# Library_v47.net
KiCad netlist of a schematic drawn in EAGLE
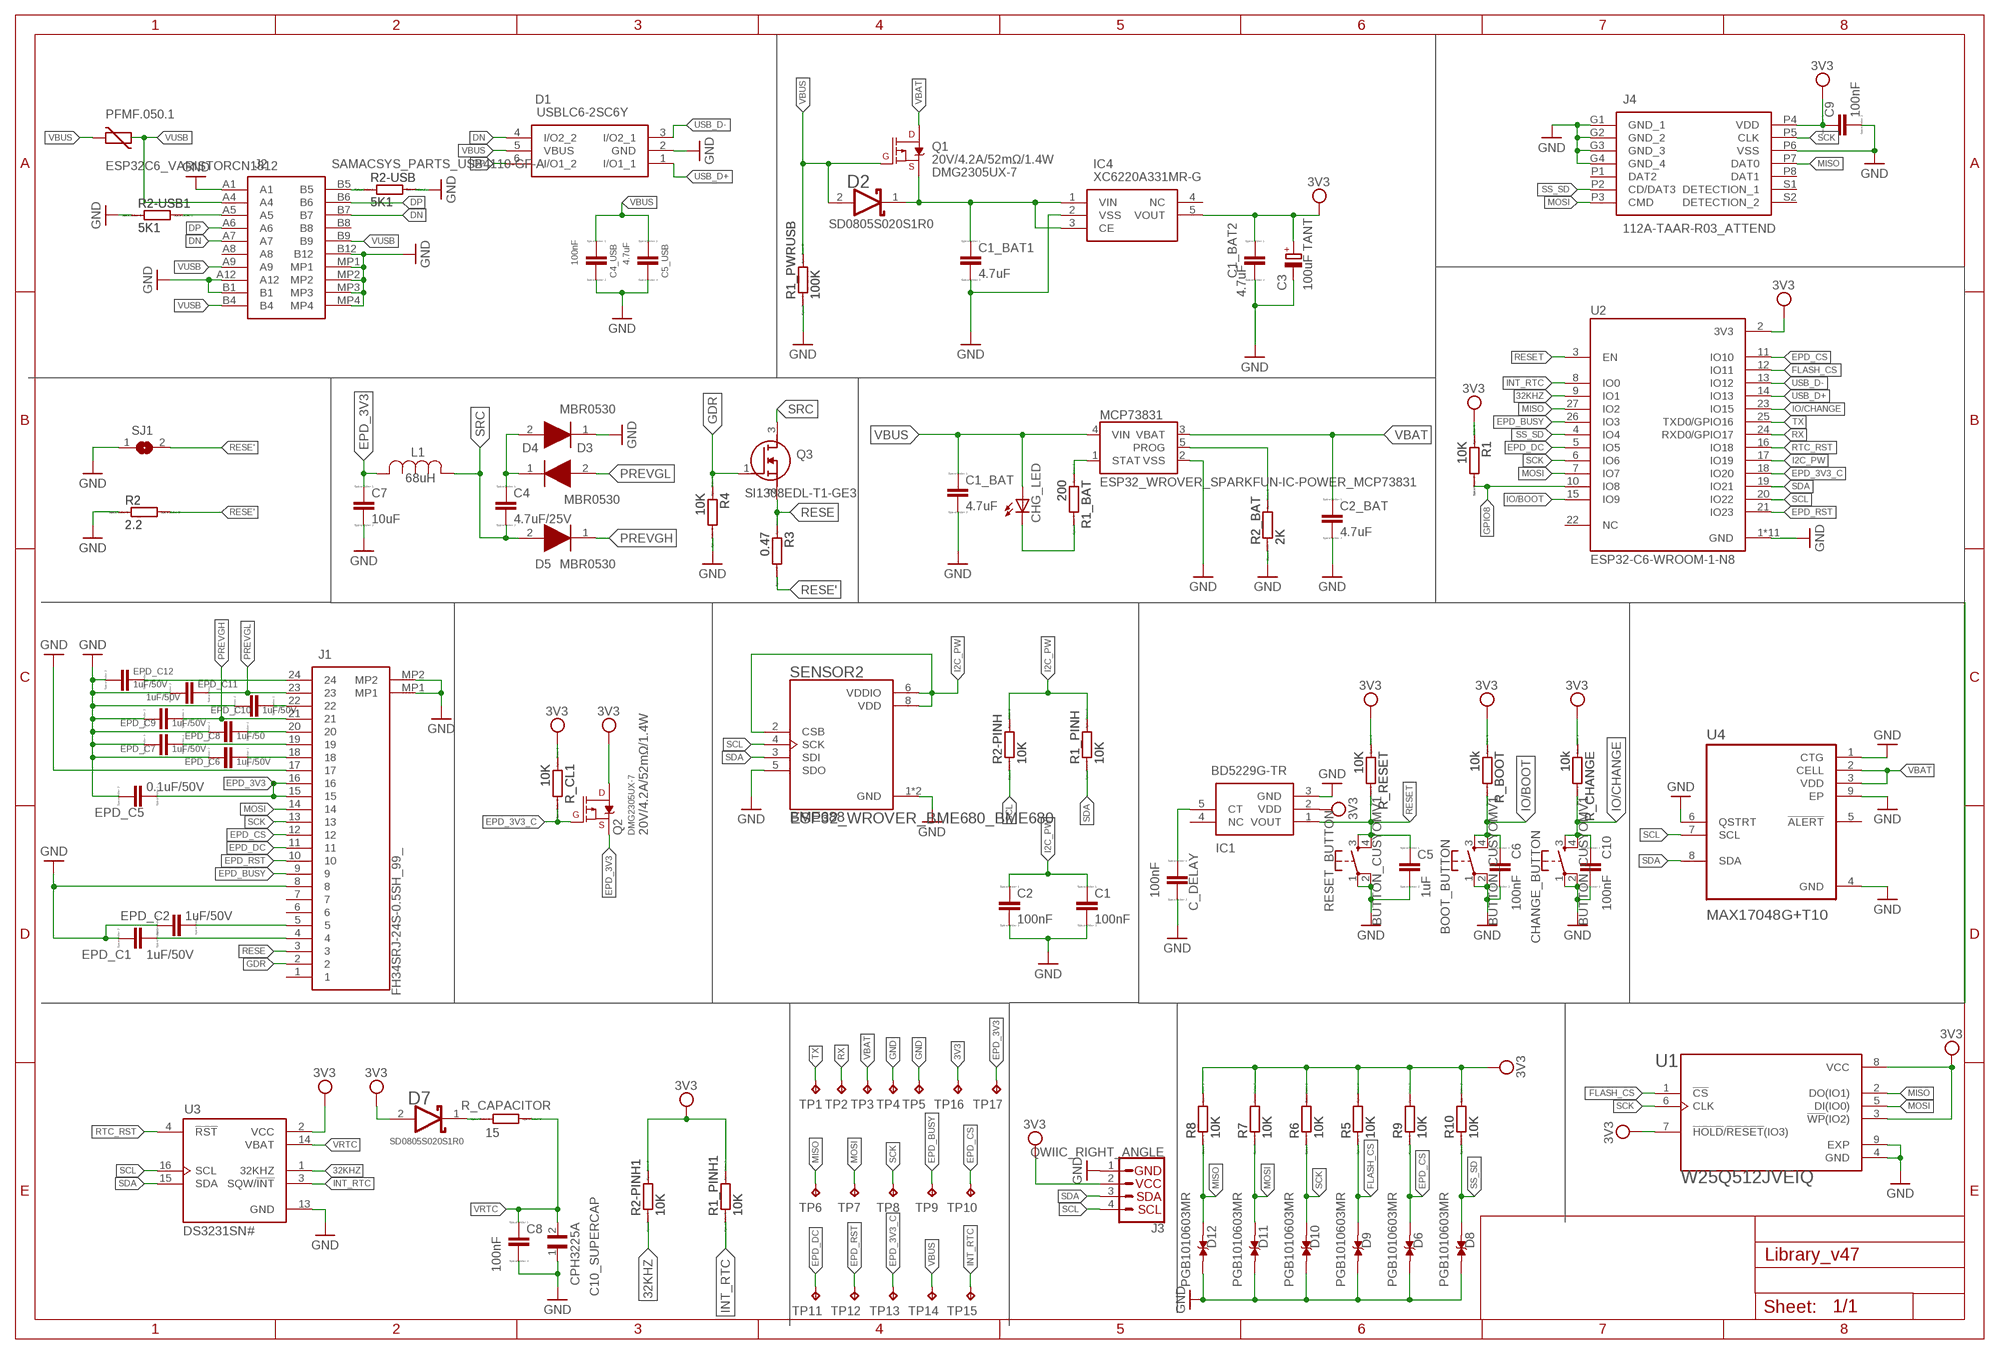
[diagram p0: schematic, sheet 1]

(export (version "E")
  (design (tool "Eeschema 10.0.6"))
  (components
    (comp (ref "BOOT_BUTTON")
      (value "BUTTON_CUSYOMV1")
      (footprint "eagle-import:MYBUTTON")
      (libsource (lib "eagle-import") (part "BUTTON_CUSYOMV1"))
    )
    (comp (ref "C1")
      (value "100nF")
      (footprint "eagle-import:ESP32_WROVER_EAGLE-LTSPICE_C0402")
      (libsource (lib "eagle-import") (part "ESP32_WROVER_EAGLE-LTSPICE_CC0402"))
    )
    (comp (ref "C1_BAT")
      (value "4.7uF")
      (footprint "eagle-import:ESP32_WROVER_EAGLE-LTSPICE_C0402")
      (libsource (lib "eagle-import") (part "ESP32_WROVER_EAGLE-LTSPICE_CC0402"))
    )
    (comp (ref "C1_BAT1")
      (value "4.7uF")
      (footprint "eagle-import:ESP32_WROVER_EAGLE-LTSPICE_C0402")
      (libsource (lib "eagle-import") (part "ESP32_WROVER_EAGLE-LTSPICE_CC0402"))
    )
    (comp (ref "C1_BAT2")
      (value "4.7uF")
      (footprint "eagle-import:ESP32_WROVER_EAGLE-LTSPICE_C0402")
      (libsource (lib "eagle-import") (part "ESP32_WROVER_EAGLE-LTSPICE_CC0402"))
    )
    (comp (ref "C2")
      (value "100nF")
      (footprint "eagle-import:ESP32_WROVER_EAGLE-LTSPICE_C0402")
      (libsource (lib "eagle-import") (part "ESP32_WROVER_EAGLE-LTSPICE_CC0402"))
    )
    (comp (ref "C2_BAT")
      (value "4.7uF")
      (footprint "eagle-import:ESP32_WROVER_EAGLE-LTSPICE_C0402")
      (libsource (lib "eagle-import") (part "ESP32_WROVER_EAGLE-LTSPICE_CC0402"))
    )
    (comp (ref "C3")
      (value "100uF TANT")
      (footprint "eagle-import:RCL_CT3528")
      (libsource (lib "eagle-import") (part "RCL_CPOL-EUCT3528"))
    )
    (comp (ref "C4")
      (value "4.7uF/25V")
      (footprint "eagle-import:ESP32_WROVER_EAGLE-LTSPICE_C0402")
      (libsource (lib "eagle-import") (part "ESP32_WROVER_EAGLE-LTSPICE_CC0402"))
    )
    (comp (ref "C4_USB")
      (value "100nF")
      (footprint "eagle-import:ESP32_WROVER_EAGLE-LTSPICE_C0402")
      (libsource (lib "eagle-import") (part "ESP32_WROVER_EAGLE-LTSPICE_CC0402"))
    )
    (comp (ref "C5")
      (value "1uF")
      (footprint "eagle-import:ESP32_WROVER_EAGLE-LTSPICE_C0402")
      (libsource (lib "eagle-import") (part "ESP32_WROVER_EAGLE-LTSPICE_CC0402"))
    )
    (comp (ref "C5_USB")
      (value "4.7uF")
      (footprint "eagle-import:ESP32_WROVER_EAGLE-LTSPICE_C0402")
      (libsource (lib "eagle-import") (part "ESP32_WROVER_EAGLE-LTSPICE_CC0402"))
    )
    (comp (ref "C6")
      (value "100nF")
      (footprint "eagle-import:ESP32_WROVER_EAGLE-LTSPICE_C0402")
      (libsource (lib "eagle-import") (part "ESP32_WROVER_EAGLE-LTSPICE_CC0402"))
    )
    (comp (ref "C7")
      (value "10uF")
      (footprint "eagle-import:ESP32_WROVER_EAGLE-LTSPICE_C0402")
      (libsource (lib "eagle-import") (part "ESP32_WROVER_EAGLE-LTSPICE_CC0402"))
    )
    (comp (ref "C8")
      (value "100nF")
      (footprint "eagle-import:ESP32_WROVER_EAGLE-LTSPICE_C0402")
      (libsource (lib "eagle-import") (part "ESP32_WROVER_EAGLE-LTSPICE_CC0402"))
    )
    (comp (ref "C9")
      (value "100nF")
      (footprint "eagle-import:ESP32_WROVER_EAGLE-LTSPICE_C0402")
      (libsource (lib "eagle-import") (part "ESP32_WROVER_EAGLE-LTSPICE_CC0402"))
    )
    (comp (ref "C10")
      (value "100nF")
      (footprint "eagle-import:ESP32_WROVER_EAGLE-LTSPICE_C0402")
      (libsource (lib "eagle-import") (part "ESP32_WROVER_EAGLE-LTSPICE_CC0402"))
    )
    (comp (ref "C10_SUPERCAP")
      (value "CPH3225A")
      (footprint "eagle-import:CAPCP3225X100N")
      (fields (field (name "MF") "Seiko Instruments"))
      (libsource (lib "eagle-import") (part "CPH3225A"))
    )
    (comp (ref "CHANGE_BUTTON")
      (value "BUTTON_CUSYOMV1")
      (footprint "eagle-import:MYBUTTON")
      (libsource (lib "eagle-import") (part "BUTTON_CUSYOMV1"))
    )
    (comp (ref "CHG_LED")
      (value "ADAFRUIT_LEDCHIP-LED0603")
      (footprint "eagle-import:ADAFRUIT_CHIP-LED0603")
      (libsource (lib "eagle-import") (part "ADAFRUIT_LEDCHIP-LED0603"))
    )
    (comp (ref "C_DELAY")
      (value "100nF")
      (footprint "eagle-import:ESP32_WROVER_EAGLE-LTSPICE_C0402")
      (libsource (lib "eagle-import") (part "ESP32_WROVER_EAGLE-LTSPICE_CC0402"))
    )
    (comp (ref "D1")
      (value "USBLC6-2SC6Y")
      (footprint "eagle-import:SOT95P280X145-6N")
      (fields (field (name "MF") "STMicroelectronics"))
      (libsource (lib "eagle-import") (part "USBLC6-2SC6Y"))
    )
    (comp (ref "D2")
      (value "ESP32_WROVER_AVX---SD0805S020S1R0_AVX_SD0805S020S1R0_0_0AVX_SD0805S020S1R0_0_0")
      (footprint "eagle-import:ESP32_WROVER_AVX---SD0805S020S1R0_AVX_SD0805S020S1R0_0")
      (fields
        (field (name "DIGIKEY_PART_NUMBER") "478-7800-1-ND")
        (field (name "MF") "AVX")
        (field (name "MOUSER_PART_NUMBER") "581-SD0805S020S1R0")
      )
      (libsource (lib "eagle-import") (part "ESP32_WROVER_AVX---SD0805S020S1R0_AVX_SD0805S020S1R0_0_0AVX_SD0805S020S1R0_0_0"))
    )
    (comp (ref "D3")
      (value "MBR0530")
      (footprint "eagle-import:SOD3716X135N")
      (fields (field (name "MF") "ON Semiconductor"))
      (libsource (lib "eagle-import") (part "MBR0530"))
    )
    (comp (ref "D4")
      (value "MBR0530")
      (footprint "eagle-import:SOD3716X135N")
      (fields (field (name "MF") "ON Semiconductor"))
      (libsource (lib "eagle-import") (part "MBR0530"))
    )
    (comp (ref "D5")
      (value "MBR0530")
      (footprint "eagle-import:SOD3716X135N")
      (fields (field (name "MF") "ON Semiconductor"))
      (libsource (lib "eagle-import") (part "MBR0530"))
    )
    (comp (ref "D6")
      (value "PGB1010603MR")
      (footprint "eagle-import:DIOC1608X36N")
      (fields (field (name "MF") "Littelfuse Inc."))
      (libsource (lib "eagle-import") (part "PGB1010603MR"))
    )
    (comp (ref "D7")
      (value "ESP32_WROVER_AVX---SD0805S020S1R0_AVX_SD0805S020S1R0_0_0AVX_SD0805S020S1R0_0_0")
      (footprint "eagle-import:ESP32_WROVER_AVX---SD0805S020S1R0_AVX_SD0805S020S1R0_0")
      (fields
        (field (name "DIGIKEY_PART_NUMBER") "478-7800-1-ND")
        (field (name "MF") "AVX")
        (field (name "MOUSER_PART_NUMBER") "581-SD0805S020S1R0")
      )
      (libsource (lib "eagle-import") (part "ESP32_WROVER_AVX---SD0805S020S1R0_AVX_SD0805S020S1R0_0_0AVX_SD0805S020S1R0_0_0"))
    )
    (comp (ref "D8")
      (value "PGB1010603MR")
      (footprint "eagle-import:DIOC1608X36N")
      (fields (field (name "MF") "Littelfuse Inc."))
      (libsource (lib "eagle-import") (part "PGB1010603MR"))
    )
    (comp (ref "D9")
      (value "PGB1010603MR")
      (footprint "eagle-import:DIOC1608X36N")
      (fields (field (name "MF") "Littelfuse Inc."))
      (libsource (lib "eagle-import") (part "PGB1010603MR"))
    )
    (comp (ref "D10")
      (value "PGB1010603MR")
      (footprint "eagle-import:DIOC1608X36N")
      (fields (field (name "MF") "Littelfuse Inc."))
      (libsource (lib "eagle-import") (part "PGB1010603MR"))
    )
    (comp (ref "D11")
      (value "PGB1010603MR")
      (footprint "eagle-import:DIOC1608X36N")
      (fields (field (name "MF") "Littelfuse Inc."))
      (libsource (lib "eagle-import") (part "PGB1010603MR"))
    )
    (comp (ref "D12")
      (value "PGB1010603MR")
      (footprint "eagle-import:DIOC1608X36N")
      (fields (field (name "MF") "Littelfuse Inc."))
      (libsource (lib "eagle-import") (part "PGB1010603MR"))
    )
    (comp (ref "EPD_C1")
      (value "1uF/50V")
      (footprint "eagle-import:ESP32_WROVER_EAGLE-LTSPICE_C0402")
      (libsource (lib "eagle-import") (part "ESP32_WROVER_EAGLE-LTSPICE_CC0402"))
    )
    (comp (ref "EPD_C2")
      (value "1uF/50V")
      (footprint "eagle-import:ESP32_WROVER_EAGLE-LTSPICE_C0402")
      (libsource (lib "eagle-import") (part "ESP32_WROVER_EAGLE-LTSPICE_CC0402"))
    )
    (comp (ref "EPD_C5")
      (value "0.1uF/50V")
      (footprint "eagle-import:ESP32_WROVER_EAGLE-LTSPICE_C0402")
      (libsource (lib "eagle-import") (part "ESP32_WROVER_EAGLE-LTSPICE_CC0402"))
    )
    (comp (ref "EPD_C6")
      (value "1uF/50V")
      (footprint "eagle-import:ESP32_WROVER_EAGLE-LTSPICE_C0402")
      (libsource (lib "eagle-import") (part "ESP32_WROVER_EAGLE-LTSPICE_CC0402"))
    )
    (comp (ref "EPD_C7")
      (value "1uF/50V")
      (footprint "eagle-import:ESP32_WROVER_EAGLE-LTSPICE_C0402")
      (libsource (lib "eagle-import") (part "ESP32_WROVER_EAGLE-LTSPICE_CC0402"))
    )
    (comp (ref "EPD_C8")
      (value "1uF/50")
      (footprint "eagle-import:ESP32_WROVER_EAGLE-LTSPICE_C0402")
      (libsource (lib "eagle-import") (part "ESP32_WROVER_EAGLE-LTSPICE_CC0402"))
    )
    (comp (ref "EPD_C9")
      (value "1uF/50V")
      (footprint "eagle-import:ESP32_WROVER_EAGLE-LTSPICE_C0402")
      (libsource (lib "eagle-import") (part "ESP32_WROVER_EAGLE-LTSPICE_CC0402"))
    )
    (comp (ref "EPD_C10")
      (value "1uF/50V")
      (footprint "eagle-import:ESP32_WROVER_EAGLE-LTSPICE_C0402")
      (libsource (lib "eagle-import") (part "ESP32_WROVER_EAGLE-LTSPICE_CC0402"))
    )
    (comp (ref "EPD_C11")
      (value "1uF/50V")
      (footprint "eagle-import:ESP32_WROVER_EAGLE-LTSPICE_C0402")
      (libsource (lib "eagle-import") (part "ESP32_WROVER_EAGLE-LTSPICE_CC0402"))
    )
    (comp (ref "EPD_C12")
      (value "1uF/50V")
      (footprint "eagle-import:ESP32_WROVER_EAGLE-LTSPICE_C0402")
      (libsource (lib "eagle-import") (part "ESP32_WROVER_EAGLE-LTSPICE_CC0402"))
    )
    (comp (ref "IC1")
      (value "BD5229G-TR")
      (footprint "eagle-import:SOT95P280X125-5N")
      (fields (field (name "MOUSER_PART_NUMBER") "755-BD5229G-TR"))
      (libsource (lib "eagle-import") (part "BD5229G-TR"))
    )
    (comp (ref "IC4")
      (value "XC6220A331MR-G")
      (footprint "eagle-import:SOT95P280X120-5N")
      (fields (field (name "MOUSER_PART_NUMBER") "865-XC6220A331MR-G"))
      (libsource (lib "eagle-import") (part "XC6220A331MR-G"))
    )
    (comp (ref "J1")
      (value "FH34SRJ-24S-0.5SH_99_")
      (footprint "eagle-import:FH34SRJ24S05SH99")
      (fields
        (field (name "MANUFACTURER_PART_NUMBER") "FH34SRJ-24S-0.5SH(99)")
        (field (name "MOUSER_PART_NUMBER") "798-FH34SRJ24S05SH99")
      )
      (libsource (lib "eagle-import") (part "FH34SRJ-24S-0.5SH_99_"))
    )
    (comp (ref "J2")
      (value "SAMACSYS_PARTS_USB4110-GF-A")
      (footprint "eagle-import:SAMACSYS_PARTS_USB4110GFA")
      (fields
        (field (name "MANUFACTURER_PART_NUMBER") "USB4110-GF-A")
        (field (name "MOUSER_PART_NUMBER") "640-USB4110-GF-A")
      )
      (libsource (lib "eagle-import") (part "SAMACSYS_PARTS_USB4110-GF-A"))
    )
    (comp (ref "J3")
      (value "QWIIC_RIGHT_ANGLE")
      (footprint "eagle-import:JST04_1MM_RA")
      (libsource (lib "eagle-import") (part "QWIIC_CONNECTORJS-1MM"))
    )
    (comp (ref "J4")
      (value "112A-TAAR-R03_ATTEND")
      (footprint "eagle-import:112ATAARR03ATTEND")
      (fields (field (name "MANUFACTURER_PART_NUMBER") "112A-TAAR-R03 ATTEND"))
      (libsource (lib "eagle-import") (part "112A-TAAR-R03_ATTEND"))
    )
    (comp (ref "L1")
      (value "68uH")
      (footprint "eagle-import:IND_4828-WE-TPC_WRE")
      (fields
        (field (name "MANUFACTURER_PART_NUMBER") "744043680")
        (field (name "COPYRIGHT") "Copyright (C) 2024 Ultra Librarian. All rights reserved.")
      )
      (libsource (lib "eagle-import") (part "744043680IND_4828-WE-TPC_WRE"))
    )
    (comp (ref "MCP73831")
      (value "ESP32_WROVER_SPARKFUN-IC-POWER_MCP73831")
      (footprint "eagle-import:ESP32_WROVER_SPARKFUN-IC-POWER_SOT23-5")
      (libsource (lib "eagle-import") (part "ESP32_WROVER_SPARKFUN-IC-POWER_MCP73831"))
    )
    (comp (ref "PFMF.050.1")
      (value "ESP32C6_VARISTORCN1812")
      (footprint "eagle-import:ESP32C6_VARISTOR_CT_CN1812")
      (libsource (lib "eagle-import") (part "ESP32C6_VARISTORCN1812"))
    )
    (comp (ref "Q1")
      (value "20V/4.2A/52mΩ/1.4W")
      (footprint "eagle-import:ESP32_WROVER_SPARKFUN-DISCRETESEMI_SOT23-3")
      (libsource (lib "eagle-import") (part "ESP32_WROVER_SPARKFUN-DISCRETESEMI_MOSFET_PCH-DMG2305UX-7"))
    )
    (comp (ref "Q2")
      (value "20V/4.2A/52mΩ/1.4W")
      (footprint "eagle-import:ESP32_WROVER_SPARKFUN-DISCRETESEMI_SOT23-3")
      (libsource (lib "eagle-import") (part "ESP32_WROVER_SPARKFUN-DISCRETESEMI_MOSFET_PCH-DMG2305UX-7"))
    )
    (comp (ref "Q3")
      (value "SI1308EDL-T1-GE3")
      (footprint "eagle-import:SOT65P210X110-3N")
      (fields (field (name "MF") "Vishay Siliconix"))
      (libsource (lib "eagle-import") (part "SI1308EDL-T1-GE3"))
    )
    (comp (ref "R1")
      (value "10K")
      (footprint "eagle-import:ESP32_WROVER_EAGLE-LTSPICE_R0402")
      (libsource (lib "eagle-import") (part "ESP32_WROVER_EAGLE-LTSPICE_RR0402"))
    )
    (comp (ref "R1_BAT")
      (value "200")
      (footprint "eagle-import:ESP32_WROVER_EAGLE-LTSPICE_R0402")
      (libsource (lib "eagle-import") (part "ESP32_WROVER_EAGLE-LTSPICE_RR0402"))
    )
    (comp (ref "R1_PINH")
      (value "10K")
      (footprint "eagle-import:ESP32_WROVER_EAGLE-LTSPICE_R0402")
      (libsource (lib "eagle-import") (part "ESP32_WROVER_EAGLE-LTSPICE_RR0402"))
    )
    (comp (ref "R1_PINH1")
      (value "10K")
      (footprint "eagle-import:ESP32_WROVER_EAGLE-LTSPICE_R0402")
      (libsource (lib "eagle-import") (part "ESP32_WROVER_EAGLE-LTSPICE_RR0402"))
    )
    (comp (ref "R1_PWRUSB")
      (value "100K")
      (footprint "eagle-import:ESP32_WROVER_EAGLE-LTSPICE_R0402")
      (libsource (lib "eagle-import") (part "ESP32_WROVER_EAGLE-LTSPICE_RR0402"))
    )
    (comp (ref "R2")
      (value "2.2")
      (footprint "eagle-import:ESP32_WROVER_EAGLE-LTSPICE_R0402")
      (libsource (lib "eagle-import") (part "ESP32_WROVER_EAGLE-LTSPICE_RR0402"))
    )
    (comp (ref "R2-PINH")
      (value "10K")
      (footprint "eagle-import:ESP32_WROVER_EAGLE-LTSPICE_R0402")
      (libsource (lib "eagle-import") (part "ESP32_WROVER_EAGLE-LTSPICE_RR0402"))
    )
    (comp (ref "R2-PINH1")
      (value "10K")
      (footprint "eagle-import:ESP32_WROVER_EAGLE-LTSPICE_R0402")
      (libsource (lib "eagle-import") (part "ESP32_WROVER_EAGLE-LTSPICE_RR0402"))
    )
    (comp (ref "R2-USB")
      (value "5K1")
      (footprint "eagle-import:ESP32_WROVER_EAGLE-LTSPICE_R0402")
      (libsource (lib "eagle-import") (part "ESP32_WROVER_EAGLE-LTSPICE_RR0402"))
    )
    (comp (ref "R2-USB1")
      (value "5K1")
      (footprint "eagle-import:ESP32_WROVER_EAGLE-LTSPICE_R0402")
      (libsource (lib "eagle-import") (part "ESP32_WROVER_EAGLE-LTSPICE_RR0402"))
    )
    (comp (ref "R2_BAT")
      (value "2K")
      (footprint "eagle-import:ESP32_WROVER_EAGLE-LTSPICE_R0402")
      (libsource (lib "eagle-import") (part "ESP32_WROVER_EAGLE-LTSPICE_RR0402"))
    )
    (comp (ref "R3")
      (value "0.47")
      (footprint "eagle-import:ESP32_WROVER_EAGLE-LTSPICE_R0402")
      (libsource (lib "eagle-import") (part "ESP32_WROVER_EAGLE-LTSPICE_RR0402"))
    )
    (comp (ref "R4")
      (value "10K")
      (footprint "eagle-import:ESP32_WROVER_EAGLE-LTSPICE_R0402")
      (libsource (lib "eagle-import") (part "ESP32_WROVER_EAGLE-LTSPICE_RR0402"))
    )
    (comp (ref "R5")
      (value "10K")
      (footprint "eagle-import:ESP32_WROVER_EAGLE-LTSPICE_R0402")
      (libsource (lib "eagle-import") (part "ESP32_WROVER_EAGLE-LTSPICE_RR0402"))
    )
    (comp (ref "R6")
      (value "10K")
      (footprint "eagle-import:ESP32_WROVER_EAGLE-LTSPICE_R0402")
      (libsource (lib "eagle-import") (part "ESP32_WROVER_EAGLE-LTSPICE_RR0402"))
    )
    (comp (ref "R7")
      (value "10K")
      (footprint "eagle-import:ESP32_WROVER_EAGLE-LTSPICE_R0402")
      (libsource (lib "eagle-import") (part "ESP32_WROVER_EAGLE-LTSPICE_RR0402"))
    )
    (comp (ref "R8")
      (value "10K")
      (footprint "eagle-import:ESP32_WROVER_EAGLE-LTSPICE_R0402")
      (libsource (lib "eagle-import") (part "ESP32_WROVER_EAGLE-LTSPICE_RR0402"))
    )
    (comp (ref "R9")
      (value "10K")
      (footprint "eagle-import:ESP32_WROVER_EAGLE-LTSPICE_R0402")
      (libsource (lib "eagle-import") (part "ESP32_WROVER_EAGLE-LTSPICE_RR0402"))
    )
    (comp (ref "R10")
      (value "10K")
      (footprint "eagle-import:ESP32_WROVER_EAGLE-LTSPICE_R0402")
      (libsource (lib "eagle-import") (part "ESP32_WROVER_EAGLE-LTSPICE_RR0402"))
    )
    (comp (ref "RESET_BUTTON")
      (value "BUTTON_CUSYOMV1")
      (footprint "eagle-import:MYBUTTON")
      (libsource (lib "eagle-import") (part "BUTTON_CUSYOMV1"))
    )
    (comp (ref "R_BOOT")
      (value "10k")
      (footprint "eagle-import:ESP32_WROVER_EAGLE-LTSPICE_R0402")
      (libsource (lib "eagle-import") (part "ESP32_WROVER_EAGLE-LTSPICE_RR0402"))
    )
    (comp (ref "R_CAPACITOR")
      (value "15")
      (footprint "eagle-import:ESP32_WROVER_EAGLE-LTSPICE_R0402")
      (libsource (lib "eagle-import") (part "ESP32_WROVER_EAGLE-LTSPICE_RR0402"))
    )
    (comp (ref "R_CHANGE")
      (value "10k")
      (footprint "eagle-import:ESP32_WROVER_EAGLE-LTSPICE_R0402")
      (libsource (lib "eagle-import") (part "ESP32_WROVER_EAGLE-LTSPICE_RR0402"))
    )
    (comp (ref "R_CL1")
      (value "10K")
      (footprint "eagle-import:ESP32_WROVER_EAGLE-LTSPICE_R0402")
      (libsource (lib "eagle-import") (part "ESP32_WROVER_EAGLE-LTSPICE_RR0402"))
    )
    (comp (ref "R_RESET")
      (value "10K")
      (footprint "eagle-import:ESP32_WROVER_EAGLE-LTSPICE_R0402")
      (libsource (lib "eagle-import") (part "ESP32_WROVER_EAGLE-LTSPICE_RR0402"))
    )
    (comp (ref "SENSOR2")
      (value "ESP32_WROVER_BME680_BME680")
      (footprint "eagle-import:ESP32_WROVER_BME680_PSON80P300X300X100-8N")
      (fields (field (name "MF") "Bosch Sensortec") (field (name "MP") "BME680"))
      (libsource (lib "eagle-import") (part "ESP32_WROVER_BME680_BME680"))
    )
    (comp (ref "SJ1") (value "SJ") (footprint "eagle-import:SJ") (libsource (lib "eagle-import") (part "SJ")))
    (comp (ref "TP1")
      (value "TPTP20R")
      (footprint "eagle-import:TP20R")
      (libsource (lib "eagle-import") (part "TPTP20R"))
    )
    (comp (ref "TP2")
      (value "TPTP20R")
      (footprint "eagle-import:TP20R")
      (libsource (lib "eagle-import") (part "TPTP20R"))
    )
    (comp (ref "TP3")
      (value "TPTP20R")
      (footprint "eagle-import:TP20R")
      (libsource (lib "eagle-import") (part "TPTP20R"))
    )
    (comp (ref "TP4")
      (value "TPTP20R")
      (footprint "eagle-import:TP20R")
      (libsource (lib "eagle-import") (part "TPTP20R"))
    )
    (comp (ref "TP5")
      (value "TPTP20R")
      (footprint "eagle-import:TP20R")
      (libsource (lib "eagle-import") (part "TPTP20R"))
    )
    (comp (ref "TP6")
      (value "TPTP20R")
      (footprint "eagle-import:TP20R")
      (libsource (lib "eagle-import") (part "TPTP20R"))
    )
    (comp (ref "TP7")
      (value "TPTP20R")
      (footprint "eagle-import:TP20R")
      (libsource (lib "eagle-import") (part "TPTP20R"))
    )
    (comp (ref "TP8")
      (value "TPTP20R")
      (footprint "eagle-import:TP20R")
      (libsource (lib "eagle-import") (part "TPTP20R"))
    )
    (comp (ref "TP9")
      (value "TPTP20R")
      (footprint "eagle-import:TP20R")
      (libsource (lib "eagle-import") (part "TPTP20R"))
    )
    (comp (ref "TP10")
      (value "TPTP20R")
      (footprint "eagle-import:TP20R")
      (libsource (lib "eagle-import") (part "TPTP20R"))
    )
    (comp (ref "TP11")
      (value "TPTP20R")
      (footprint "eagle-import:TP20R")
      (libsource (lib "eagle-import") (part "TPTP20R"))
    )
    (comp (ref "TP12")
      (value "TPTP20R")
      (footprint "eagle-import:TP20R")
      (libsource (lib "eagle-import") (part "TPTP20R"))
    )
    (comp (ref "TP13")
      (value "TPTP20R")
      (footprint "eagle-import:TP20R")
      (libsource (lib "eagle-import") (part "TPTP20R"))
    )
    (comp (ref "TP14")
      (value "TPTP20R")
      (footprint "eagle-import:TP20R")
      (libsource (lib "eagle-import") (part "TPTP20R"))
    )
    (comp (ref "TP15")
      (value "TPTP20R")
      (footprint "eagle-import:TP20R")
      (libsource (lib "eagle-import") (part "TPTP20R"))
    )
    (comp (ref "TP16")
      (value "TPTP20R")
      (footprint "eagle-import:TP20R")
      (libsource (lib "eagle-import") (part "TPTP20R"))
    )
    (comp (ref "TP17")
      (value "TPTP20R")
      (footprint "eagle-import:TP20R")
      (libsource (lib "eagle-import") (part "TPTP20R"))
    )
    (comp (ref "U1")
      (value "W25Q512JVEIQ")
      (footprint "eagle-import:SON127P600X800X80-9N")
      (fields (field (name "MF") "Winbond Electronics"))
      (libsource (lib "eagle-import") (part "W25Q512JVEIQ"))
    )
    (comp (ref "U2")
      (value "ESP32-C6-WROOM-1-N8")
      (footprint "eagle-import:XCVR_ESP32-C6-WROOM-1-N8")
      (fields (field (name "MF") "Espressif Systems"))
      (libsource (lib "eagle-import") (part "ESP32-C6-WROOM-1-N8"))
    )
    (comp (ref "U3")
      (value "DS3231SN#")
      (footprint "eagle-import:SOIC127P1032X265-16N")
      (fields (field (name "MF") "Analog Devices"))
      (libsource (lib "eagle-import") (part "DS3231SN#"))
    )
    (comp (ref "U4")
      (value "MAX17048G+T10")
      (footprint "eagle-import:SON50P200X200X80-9N")
      (fields (field (name "MF") "Analog Devices"))
      (libsource (lib "eagle-import") (part "MAX17048G+T10"))
    )
  )
  (nets
    (net (code "1") (name "3V3") (class "Default")
      (node (ref "C1_BAT2") (pin "1") (pinfunction "1_1") (pintype "passive"))
      (node (ref "C3") (pin "+") (pinfunction "+_+") (pintype "passive"))
      (node (ref "C9") (pin "1") (pinfunction "1_1") (pintype "passive"))
      (node (ref "D7") (pin "2") (pinfunction "ANODE_2") (pintype "bidirectional"))
      (node (ref "IC1") (pin "2") (pinfunction "VDD_2") (pintype "bidirectional"))
      (node (ref "IC4") (pin "5") (pinfunction "VOUT_5") (pintype "bidirectional"))
      (node (ref "J3") (pin "2") (pinfunction "2_2") (pintype "power_in"))
      (node (ref "J4") (pin "P4") (pinfunction "VDD_P4") (pintype "bidirectional"))
      (node (ref "Q2") (pin "3") (pinfunction "D_3") (pintype "bidirectional"))
      (node (ref "R1") (pin "1") (pinfunction "1_1") (pintype "passive"))
      (node (ref "R10") (pin "2") (pinfunction "2_2") (pintype "passive"))
      (node (ref "R1_PINH1") (pin "2") (pinfunction "2_2") (pintype "passive"))
      (node (ref "R2-PINH1") (pin "2") (pinfunction "2_2") (pintype "passive"))
      (node (ref "R5") (pin "2") (pinfunction "2_2") (pintype "passive"))
      (node (ref "R6") (pin "2") (pinfunction "2_2") (pintype "passive"))
      (node (ref "R7") (pin "2") (pinfunction "2_2") (pintype "passive"))
      (node (ref "R8") (pin "2") (pinfunction "2_2") (pintype "passive"))
      (node (ref "R9") (pin "2") (pinfunction "2_2") (pintype "passive"))
      (node (ref "R_BOOT") (pin "1") (pinfunction "1_1") (pintype "passive"))
      (node (ref "R_CHANGE") (pin "1") (pinfunction "1_1") (pintype "passive"))
      (node (ref "R_CL1") (pin "1") (pinfunction "1_1") (pintype "passive"))
      (node (ref "R_RESET") (pin "1") (pinfunction "1_1") (pintype "passive"))
      (node (ref "TP16") (pin "TP") (pinfunction "TP_TP") (pintype "input"))
      (node (ref "U1") (pin "3") (pinfunction "~{WP}(IO2)_3") (pintype "bidirectional"))
      (node (ref "U1") (pin "7") (pinfunction "~{HOLD}/~{RESET}(IO3)_7") (pintype "bidirectional"))
      (node (ref "U1") (pin "8") (pinfunction "VCC_8") (pintype "power_in"))
      (node (ref "U2") (pin "2") (pinfunction "3V3_2") (pintype "power_in"))
      (node (ref "U3") (pin "2") (pinfunction "VCC_2") (pintype "power_in"))
    )
    (net (code "2") (name "32KHZ") (class "Default")
      (node (ref "R2-PINH1") (pin "1") (pinfunction "1_1") (pintype "passive"))
      (node (ref "U2") (pin "9") (pinfunction "IO1_9") (pintype "bidirectional"))
      (node (ref "U3") (pin "1") (pinfunction "32KHZ_1") (pintype "output"))
    )
    (net (code "3") (name "DN") (class "Default")
      (node (ref "D1") (pin "4") (pinfunction "I/O2_2_4") (pintype "bidirectional"))
      (node (ref "J2") (pin "A7") (pinfunction "A7_A7") (pintype "bidirectional"))
      (node (ref "J2") (pin "B7") (pinfunction "B7_B7") (pintype "bidirectional"))
    )
    (net (code "4") (name "DP") (class "Default")
      (node (ref "D1") (pin "6") (pinfunction "I/O1_2_6") (pintype "bidirectional"))
      (node (ref "J2") (pin "A6") (pinfunction "A6_A6") (pintype "bidirectional"))
      (node (ref "J2") (pin "B6") (pinfunction "B6_B6") (pintype "bidirectional"))
    )
    (net (code "5") (name "EPD_3V3") (class "Default")
      (node (ref "C7") (pin "1") (pinfunction "1_1") (pintype "passive"))
      (node (ref "EPD_C5") (pin "1") (pinfunction "1_1") (pintype "passive"))
      (node (ref "J1") (pin "15") (pinfunction "15_15") (pintype "bidirectional"))
      (node (ref "J1") (pin "16") (pinfunction "16_16") (pintype "bidirectional"))
      (node (ref "L1") (pin "2") (pinfunction "2_2") (pintype "passive"))
      (node (ref "Q2") (pin "2") (pinfunction "S_2") (pintype "bidirectional"))
      (node (ref "TP17") (pin "TP") (pinfunction "TP_TP") (pintype "input"))
    )
    (net (code "6") (name "EPD_3V3_C") (class "Default")
      (node (ref "Q2") (pin "1") (pinfunction "G_1") (pintype "bidirectional"))
      (node (ref "R_CL1") (pin "2") (pinfunction "2_2") (pintype "passive"))
      (node (ref "TP13") (pin "TP") (pinfunction "TP_TP") (pintype "input"))
      (node (ref "U2") (pin "18") (pinfunction "IO20_18") (pintype "bidirectional"))
    )
    (net (code "7") (name "EPD_BUSY") (class "Default")
      (node (ref "J1") (pin "9") (pinfunction "9_9") (pintype "bidirectional"))
      (node (ref "TP9") (pin "TP") (pinfunction "TP_TP") (pintype "input"))
      (node (ref "U2") (pin "26") (pinfunction "IO3_26") (pintype "bidirectional"))
    )
    (net (code "8") (name "EPD_CS") (class "Default")
      (node (ref "D6") (pin "2") (pinfunction "2_2") (pintype "passive"))
      (node (ref "J1") (pin "12") (pinfunction "12_12") (pintype "bidirectional"))
      (node (ref "R9") (pin "1") (pinfunction "1_1") (pintype "passive"))
      (node (ref "TP10") (pin "TP") (pinfunction "TP_TP") (pintype "input"))
      (node (ref "U2") (pin "11") (pinfunction "IO10_11") (pintype "bidirectional"))
    )
    (net (code "9") (name "EPD_DC") (class "Default")
      (node (ref "J1") (pin "11") (pinfunction "11_11") (pintype "bidirectional"))
      (node (ref "TP11") (pin "TP") (pinfunction "TP_TP") (pintype "input"))
      (node (ref "U2") (pin "5") (pinfunction "IO5_5") (pintype "bidirectional"))
    )
    (net (code "10") (name "EPD_RST") (class "Default")
      (node (ref "J1") (pin "10") (pinfunction "10_10") (pintype "bidirectional"))
      (node (ref "TP12") (pin "TP") (pinfunction "TP_TP") (pintype "input"))
      (node (ref "U2") (pin "21") (pinfunction "IO23_21") (pintype "bidirectional"))
    )
    (net (code "11") (name "FLASH_CS") (class "Default")
      (node (ref "D9") (pin "2") (pinfunction "2_2") (pintype "passive"))
      (node (ref "R5") (pin "1") (pinfunction "1_1") (pintype "passive"))
      (node (ref "U1") (pin "1") (pinfunction "~{CS}_1") (pintype "input"))
      (node (ref "U2") (pin "12") (pinfunction "IO11_12") (pintype "bidirectional"))
    )
    (net (code "12") (name "GDR") (class "Default")
      (node (ref "J1") (pin "2") (pinfunction "2_2") (pintype "bidirectional"))
      (node (ref "Q3") (pin "1") (pinfunction "G_1") (pintype "bidirectional"))
      (node (ref "R4") (pin "1") (pinfunction "1_1") (pintype "passive"))
    )
    (net (code "13") (name "GND") (class "Default")
      (node (ref "BOOT_BUTTON") (pin "1") (pinfunction "1_1") (pintype "passive"))
      (node (ref "BOOT_BUTTON") (pin "2") (pinfunction "2_2") (pintype "passive"))
      (node (ref "C1") (pin "2") (pinfunction "2_2") (pintype "passive"))
      (node (ref "C10") (pin "2") (pinfunction "2_2") (pintype "passive"))
      (node (ref "C10_SUPERCAP") (pin "1") (pinfunction "1_1") (pintype "passive"))
      (node (ref "C1_BAT") (pin "2") (pinfunction "2_2") (pintype "passive"))
      (node (ref "C1_BAT1") (pin "2") (pinfunction "2_2") (pintype "passive"))
      (node (ref "C1_BAT2") (pin "2") (pinfunction "2_2") (pintype "passive"))
      (node (ref "C2") (pin "2") (pinfunction "2_2") (pintype "passive"))
      (node (ref "C2_BAT") (pin "2") (pinfunction "2_2") (pintype "passive"))
      (node (ref "C3") (pin "-") (pinfunction "-_-") (pintype "passive"))
      (node (ref "C4_USB") (pin "2") (pinfunction "2_2") (pintype "passive"))
      (node (ref "C5") (pin "2") (pinfunction "2_2") (pintype "passive"))
      (node (ref "C5_USB") (pin "2") (pinfunction "2_2") (pintype "passive"))
      (node (ref "C6") (pin "2") (pinfunction "2_2") (pintype "passive"))
      (node (ref "C7") (pin "2") (pinfunction "2_2") (pintype "passive"))
      (node (ref "C8") (pin "2") (pinfunction "2_2") (pintype "passive"))
      (node (ref "C9") (pin "2") (pinfunction "2_2") (pintype "passive"))
      (node (ref "CHANGE_BUTTON") (pin "1") (pinfunction "1_1") (pintype "passive"))
      (node (ref "CHANGE_BUTTON") (pin "2") (pinfunction "2_2") (pintype "passive"))
      (node (ref "C_DELAY") (pin "2") (pinfunction "2_2") (pintype "passive"))
      (node (ref "D1") (pin "2") (pinfunction "GND_2") (pintype "bidirectional"))
      (node (ref "D10") (pin "1") (pinfunction "1_1") (pintype "passive"))
      (node (ref "D11") (pin "1") (pinfunction "1_1") (pintype "passive"))
      (node (ref "D12") (pin "1") (pinfunction "1_1") (pintype "passive"))
      (node (ref "D4") (pin "1") (pinfunction "K_1") (pintype "bidirectional"))
      (node (ref "D6") (pin "1") (pinfunction "1_1") (pintype "passive"))
      (node (ref "D8") (pin "1") (pinfunction "1_1") (pintype "passive"))
      (node (ref "D9") (pin "1") (pinfunction "1_1") (pintype "passive"))
      (node (ref "EPD_C1") (pin "2") (pinfunction "2_2") (pintype "passive"))
      (node (ref "EPD_C10") (pin "2") (pinfunction "2_2") (pintype "passive"))
      (node (ref "EPD_C11") (pin "2") (pinfunction "2_2") (pintype "passive"))
      (node (ref "EPD_C12") (pin "2") (pinfunction "2_2") (pintype "passive"))
      (node (ref "EPD_C2") (pin "2") (pinfunction "2_2") (pintype "passive"))
      (node (ref "EPD_C5") (pin "2") (pinfunction "2_2") (pintype "passive"))
      (node (ref "EPD_C6") (pin "2") (pinfunction "2_2") (pintype "passive"))
      (node (ref "EPD_C7") (pin "2") (pinfunction "2_2") (pintype "passive"))
      (node (ref "EPD_C8") (pin "2") (pinfunction "2_2") (pintype "passive"))
      (node (ref "EPD_C9") (pin "2") (pinfunction "2_2") (pintype "passive"))
      (node (ref "IC1") (pin "3") (pinfunction "GND_3") (pintype "bidirectional"))
      (node (ref "IC4") (pin "2") (pinfunction "VSS_2") (pintype "bidirectional"))
      (node (ref "J1") (pin "17") (pinfunction "17_17") (pintype "bidirectional"))
      (node (ref "J1") (pin "8") (pinfunction "8_8") (pintype "bidirectional"))
      (node (ref "J1") (pin "MP1") (pinfunction "MP1_MP1") (pintype "bidirectional"))
      (node (ref "J1") (pin "MP2") (pinfunction "MP2_MP2") (pintype "bidirectional"))
      (node (ref "J2") (pin "A1") (pinfunction "A1_A1") (pintype "bidirectional"))
      (node (ref "J2") (pin "A12") (pinfunction "A12_A12") (pintype "bidirectional"))
      (node (ref "J2") (pin "B1") (pinfunction "B1_B1") (pintype "bidirectional"))
      (node (ref "J2") (pin "B12") (pinfunction "B12_B12") (pintype "bidirectional"))
      (node (ref "J2") (pin "MP1") (pinfunction "MP1_MP1") (pintype "bidirectional"))
      (node (ref "J2") (pin "MP2") (pinfunction "MP2_MP2") (pintype "bidirectional"))
      (node (ref "J2") (pin "MP3") (pinfunction "MP3_MP3") (pintype "bidirectional"))
      (node (ref "J2") (pin "MP4") (pinfunction "MP4_MP4") (pintype "bidirectional"))
      (node (ref "J3") (pin "1") (pinfunction "1_1") (pintype "power_in"))
      (node (ref "J4") (pin "G1") (pinfunction "GND_1_G1") (pintype "bidirectional"))
      (node (ref "J4") (pin "G2") (pinfunction "GND_2_G2") (pintype "bidirectional"))
      (node (ref "J4") (pin "G3") (pinfunction "GND_3_G3") (pintype "bidirectional"))
      (node (ref "J4") (pin "G4") (pinfunction "GND_4_G4") (pintype "bidirectional"))
      (node (ref "J4") (pin "P6") (pinfunction "VSS_P6") (pintype "bidirectional"))
      (node (ref "MCP73831") (pin "2") (pinfunction "VSS_2") (pintype "power_in"))
      (node (ref "R1_PWRUSB") (pin "1") (pinfunction "1_1") (pintype "passive"))
      (node (ref "R2") (pin "1") (pinfunction "1_1") (pintype "passive"))
      (node (ref "R2-USB") (pin "2") (pinfunction "2_2") (pintype "passive"))
      (node (ref "R2-USB1") (pin "1") (pinfunction "1_1") (pintype "passive"))
      (node (ref "R2_BAT") (pin "1") (pinfunction "1_1") (pintype "passive"))
      (node (ref "R4") (pin "2") (pinfunction "2_2") (pintype "passive"))
      (node (ref "RESET_BUTTON") (pin "1") (pinfunction "1_1") (pintype "passive"))
      (node (ref "RESET_BUTTON") (pin "2") (pinfunction "2_2") (pintype "passive"))
      (node (ref "SENSOR2") (pin "1") (pinfunction "GND_1") (pintype "power_in"))
      (node (ref "SENSOR2") (pin "5") (pinfunction "SDO_5") (pintype "bidirectional"))
      (node (ref "SENSOR2") (pin "7") (pinfunction "GND_7") (pintype "power_in"))
      (node (ref "SJ1") (pin "1") (pinfunction "1_1") (pintype "passive"))
      (node (ref "TP4") (pin "TP") (pinfunction "TP_TP") (pintype "input"))
      (node (ref "TP5") (pin "TP") (pinfunction "TP_TP") (pintype "input"))
      (node (ref "U1") (pin "4") (pinfunction "GND_4") (pintype "power_in"))
      (node (ref "U1") (pin "9") (pinfunction "EXP_9") (pintype "passive"))
      (node (ref "U2") (pin "1") (pinfunction "GND_1") (pintype "power_in"))
      (node (ref "U2") (pin "28") (pinfunction "GND_28") (pintype "power_in"))
      (node (ref "U2") (pin "29_1") (pinfunction "GND_29_1") (pintype "power_in"))
      (node (ref "U2") (pin "29_2") (pinfunction "GND_29_2") (pintype "power_in"))
      (node (ref "U2") (pin "29_3") (pinfunction "GND_29_3") (pintype "power_in"))
      (node (ref "U2") (pin "29_4") (pinfunction "GND_29_4") (pintype "power_in"))
      (node (ref "U2") (pin "29_5") (pinfunction "GND_29_5") (pintype "power_in"))
      (node (ref "U2") (pin "29_6") (pinfunction "GND_29_6") (pintype "power_in"))
      (node (ref "U2") (pin "29_7") (pinfunction "GND_29_7") (pintype "power_in"))
      (node (ref "U2") (pin "29_8") (pinfunction "GND_29_8") (pintype "power_in"))
      (node (ref "U2") (pin "29_9") (pinfunction "GND_29_9") (pintype "power_in"))
      (node (ref "U3") (pin "13") (pinfunction "GND_13") (pintype "power_in"))
      (node (ref "U4") (pin "1") (pinfunction "CTG_1") (pintype "power_in"))
      (node (ref "U4") (pin "4") (pinfunction "GND_4") (pintype "power_in"))
      (node (ref "U4") (pin "6") (pinfunction "QSTRT_6") (pintype "input"))
      (node (ref "U4") (pin "9") (pinfunction "EP_9") (pintype "power_in"))
    )
    (net (code "14") (name "GPIO8") (class "Default")
      (node (ref "R1") (pin "2") (pinfunction "2_2") (pintype "passive"))
      (node (ref "U2") (pin "10") (pinfunction "IO8_10") (pintype "bidirectional"))
    )
    (net (code "15") (name "I2C_PW") (class "Default")
      (node (ref "C1") (pin "1") (pinfunction "1_1") (pintype "passive"))
      (node (ref "C2") (pin "1") (pinfunction "1_1") (pintype "passive"))
      (node (ref "R1_PINH") (pin "2") (pinfunction "2_2") (pintype "passive"))
      (node (ref "R2-PINH") (pin "2") (pinfunction "2_2") (pintype "passive"))
      (node (ref "SENSOR2") (pin "2") (pinfunction "CSB_2") (pintype "input"))
      (node (ref "SENSOR2") (pin "6") (pinfunction "VDDIO_6") (pintype "power_in"))
      (node (ref "SENSOR2") (pin "8") (pinfunction "VDD_8") (pintype "power_in"))
      (node (ref "U2") (pin "17") (pinfunction "IO19_17") (pintype "bidirectional"))
    )
    (net (code "16") (name "INT_RTC") (class "Default")
      (node (ref "R1_PINH1") (pin "1") (pinfunction "1_1") (pintype "passive"))
      (node (ref "TP15") (pin "TP") (pinfunction "TP_TP") (pintype "input"))
      (node (ref "U2") (pin "8") (pinfunction "IO0_8") (pintype "bidirectional"))
      (node (ref "U3") (pin "3") (pinfunction "SQW/~{INT}_3") (pintype "output"))
    )
    (net (code "17") (name "IO{slash}BOOT") (class "Default")
      (node (ref "BOOT_BUTTON") (pin "3") (pinfunction "3_3") (pintype "passive"))
      (node (ref "BOOT_BUTTON") (pin "4") (pinfunction "4_4") (pintype "passive"))
      (node (ref "C6") (pin "1") (pinfunction "1_1") (pintype "passive"))
      (node (ref "R_BOOT") (pin "2") (pinfunction "2_2") (pintype "passive"))
      (node (ref "U2") (pin "15") (pinfunction "IO9_15") (pintype "bidirectional"))
    )
    (net (code "18") (name "IO{slash}CHANGE") (class "Default")
      (node (ref "C10") (pin "1") (pinfunction "1_1") (pintype "passive"))
      (node (ref "CHANGE_BUTTON") (pin "3") (pinfunction "3_3") (pintype "passive"))
      (node (ref "CHANGE_BUTTON") (pin "4") (pinfunction "4_4") (pintype "passive"))
      (node (ref "R_CHANGE") (pin "2") (pinfunction "2_2") (pintype "passive"))
      (node (ref "U2") (pin "23") (pinfunction "IO15_23") (pintype "bidirectional"))
    )
    (net (code "19") (name "MISO") (class "Default")
      (node (ref "D12") (pin "2") (pinfunction "2_2") (pintype "passive"))
      (node (ref "J4") (pin "P7") (pinfunction "DAT0_P7") (pintype "bidirectional"))
      (node (ref "R8") (pin "1") (pinfunction "1_1") (pintype "passive"))
      (node (ref "TP6") (pin "TP") (pinfunction "TP_TP") (pintype "input"))
      (node (ref "U1") (pin "2") (pinfunction "DO(IO1)_2") (pintype "bidirectional"))
      (node (ref "U2") (pin "27") (pinfunction "IO2_27") (pintype "bidirectional"))
    )
    (net (code "20") (name "MOSI") (class "Default")
      (node (ref "D11") (pin "2") (pinfunction "2_2") (pintype "passive"))
      (node (ref "J1") (pin "14") (pinfunction "14_14") (pintype "bidirectional"))
      (node (ref "J4") (pin "P3") (pinfunction "CMD_P3") (pintype "bidirectional"))
      (node (ref "R7") (pin "1") (pinfunction "1_1") (pintype "passive"))
      (node (ref "TP7") (pin "TP") (pinfunction "TP_TP") (pintype "input"))
      (node (ref "U1") (pin "5") (pinfunction "DI(IO0)_5") (pintype "bidirectional"))
      (node (ref "U2") (pin "7") (pinfunction "IO7_7") (pintype "bidirectional"))
    )
    (net (code "21") (name "Net-(CHG_LED-PadC)") (class "Default")
      (node (ref "CHG_LED") (pin "C") (pinfunction "C_C") (pintype "passive"))
      (node (ref "R1_BAT") (pin "2") (pinfunction "2_2") (pintype "passive"))
    )
    (net (code "22") (name "Net-(D2-CATHODE)") (class "Default")
      (node (ref "C1_BAT1") (pin "1") (pinfunction "1_1") (pintype "passive"))
      (node (ref "D2") (pin "1") (pinfunction "CATHODE_1") (pintype "bidirectional"))
      (node (ref "IC4") (pin "1") (pinfunction "VIN_1") (pintype "bidirectional"))
      (node (ref "IC4") (pin "3") (pinfunction "CE_3") (pintype "bidirectional"))
      (node (ref "Q1") (pin "2") (pinfunction "S_2") (pintype "bidirectional"))
    )
    (net (code "23") (name "Net-(D3-K)") (class "Default")
      (node (ref "C4") (pin "1") (pinfunction "1_1") (pintype "passive"))
      (node (ref "D3") (pin "1") (pinfunction "K_1") (pintype "bidirectional"))
      (node (ref "D4") (pin "2") (pinfunction "A_2") (pintype "bidirectional"))
    )
    (net (code "24") (name "Net-(D7-CATHODE)") (class "Default")
      (node (ref "D7") (pin "1") (pinfunction "CATHODE_1") (pintype "bidirectional"))
      (node (ref "R_CAPACITOR") (pin "2") (pinfunction "2_2") (pintype "passive"))
    )
    (net (code "25") (name "Net-(EPD_C1-Pad1)") (class "Default")
      (node (ref "EPD_C1") (pin "1") (pinfunction "1_1") (pintype "passive"))
      (node (ref "J1") (pin "4") (pinfunction "4_4") (pintype "bidirectional"))
    )
    (net (code "26") (name "Net-(EPD_C2-Pad1)") (class "Default")
      (node (ref "EPD_C2") (pin "1") (pinfunction "1_1") (pintype "passive"))
      (node (ref "J1") (pin "5") (pinfunction "5_5") (pintype "bidirectional"))
    )
    (net (code "27") (name "Net-(EPD_C6-Pad1)") (class "Default")
      (node (ref "EPD_C6") (pin "1") (pinfunction "1_1") (pintype "passive"))
      (node (ref "J1") (pin "18") (pinfunction "18_18") (pintype "bidirectional"))
    )
    (net (code "28") (name "Net-(EPD_C7-Pad1)") (class "Default")
      (node (ref "EPD_C7") (pin "1") (pinfunction "1_1") (pintype "passive"))
      (node (ref "J1") (pin "19") (pinfunction "19_19") (pintype "bidirectional"))
    )
    (net (code "29") (name "Net-(EPD_C8-Pad1)") (class "Default")
      (node (ref "EPD_C8") (pin "1") (pinfunction "1_1") (pintype "passive"))
      (node (ref "J1") (pin "20") (pinfunction "20_20") (pintype "bidirectional"))
    )
    (net (code "30") (name "Net-(EPD_C10-Pad1)") (class "Default")
      (node (ref "EPD_C10") (pin "1") (pinfunction "1_1") (pintype "passive"))
      (node (ref "J1") (pin "22") (pinfunction "22_22") (pintype "bidirectional"))
    )
    (net (code "31") (name "Net-(EPD_C12-Pad1)") (class "Default")
      (node (ref "EPD_C12") (pin "1") (pinfunction "1_1") (pintype "passive"))
      (node (ref "J1") (pin "24") (pinfunction "24_24") (pintype "bidirectional"))
    )
    (net (code "32") (name "Net-(IC1-CT)") (class "Default")
      (node (ref "C_DELAY") (pin "1") (pinfunction "1_1") (pintype "passive"))
      (node (ref "IC1") (pin "5") (pinfunction "CT_5") (pintype "bidirectional"))
    )
    (net (code "33") (name "Net-(J2-PadA5)") (class "Default")
      (node (ref "J2") (pin "A5") (pinfunction "A5_A5") (pintype "bidirectional"))
      (node (ref "R2-USB1") (pin "2") (pinfunction "2_2") (pintype "passive"))
    )
    (net (code "34") (name "Net-(J2-PadB5)") (class "Default")
      (node (ref "J2") (pin "B5") (pinfunction "B5_B5") (pintype "bidirectional"))
      (node (ref "R2-USB") (pin "1") (pinfunction "1_1") (pintype "passive"))
    )
    (net (code "35") (name "Net-(MCP73831-PROG)") (class "Default")
      (node (ref "MCP73831") (pin "5") (pinfunction "PROG_5") (pintype "input"))
      (node (ref "R2_BAT") (pin "2") (pinfunction "2_2") (pintype "passive"))
    )
    (net (code "36") (name "Net-(MCP73831-STAT)") (class "Default")
      (node (ref "MCP73831") (pin "1") (pinfunction "STAT_1") (pintype "output"))
      (node (ref "R1_BAT") (pin "1") (pinfunction "1_1") (pintype "passive"))
    )
    (net (code "37") (name "PREVGH") (class "Default")
      (node (ref "D5") (pin "1") (pinfunction "K_1") (pintype "bidirectional"))
      (node (ref "EPD_C9") (pin "1") (pinfunction "1_1") (pintype "passive"))
      (node (ref "J1") (pin "21") (pinfunction "21_21") (pintype "bidirectional"))
    )
    (net (code "38") (name "PREVGL") (class "Default")
      (node (ref "D3") (pin "2") (pinfunction "A_2") (pintype "bidirectional"))
      (node (ref "EPD_C11") (pin "1") (pinfunction "1_1") (pintype "passive"))
      (node (ref "J1") (pin "23") (pinfunction "23_23") (pintype "bidirectional"))
    )
    (net (code "39") (name "RESE") (class "Default")
      (node (ref "J1") (pin "3") (pinfunction "3_3") (pintype "bidirectional"))
      (node (ref "Q3") (pin "2") (pinfunction "S_2") (pintype "bidirectional"))
      (node (ref "R3") (pin "1") (pinfunction "1_1") (pintype "passive"))
    )
    (net (code "40") (name "RESE'") (class "Default")
      (node (ref "R2") (pin "2") (pinfunction "2_2") (pintype "passive"))
      (node (ref "R3") (pin "2") (pinfunction "2_2") (pintype "passive"))
      (node (ref "SJ1") (pin "2") (pinfunction "2_2") (pintype "passive"))
    )
    (net (code "41") (name "RESET") (class "Default")
      (node (ref "C5") (pin "1") (pinfunction "1_1") (pintype "passive"))
      (node (ref "IC1") (pin "1") (pinfunction "VOUT_1") (pintype "bidirectional"))
      (node (ref "RESET_BUTTON") (pin "3") (pinfunction "3_3") (pintype "passive"))
      (node (ref "RESET_BUTTON") (pin "4") (pinfunction "4_4") (pintype "passive"))
      (node (ref "R_RESET") (pin "2") (pinfunction "2_2") (pintype "passive"))
      (node (ref "U2") (pin "3") (pinfunction "EN_3") (pintype "input"))
    )
    (net (code "42") (name "RTC_RST") (class "Default")
      (node (ref "U2") (pin "16") (pinfunction "IO18_16") (pintype "bidirectional"))
      (node (ref "U3") (pin "4") (pinfunction "~{RST}_4") (pintype "input"))
    )
    (net (code "43") (name "RX") (class "Default")
      (node (ref "TP2") (pin "TP") (pinfunction "TP_TP") (pintype "input"))
      (node (ref "U2") (pin "24") (pinfunction "RXD0/GPIO17_24") (pintype "bidirectional"))
    )
    (net (code "44") (name "SCK") (class "Default")
      (node (ref "D10") (pin "2") (pinfunction "2_2") (pintype "passive"))
      (node (ref "J1") (pin "13") (pinfunction "13_13") (pintype "bidirectional"))
      (node (ref "J4") (pin "P5") (pinfunction "CLK_P5") (pintype "bidirectional"))
      (node (ref "R6") (pin "1") (pinfunction "1_1") (pintype "passive"))
      (node (ref "TP8") (pin "TP") (pinfunction "TP_TP") (pintype "input"))
      (node (ref "U1") (pin "6") (pinfunction "CLK_6") (pintype "input"))
      (node (ref "U2") (pin "6") (pinfunction "IO6_6") (pintype "bidirectional"))
    )
    (net (code "45") (name "SCL") (class "Default")
      (node (ref "J3") (pin "4") (pinfunction "4_4") (pintype "passive"))
      (node (ref "R2-PINH") (pin "1") (pinfunction "1_1") (pintype "passive"))
      (node (ref "SENSOR2") (pin "4") (pinfunction "SCK_4") (pintype "input"))
      (node (ref "U2") (pin "20") (pinfunction "IO22_20") (pintype "bidirectional"))
      (node (ref "U3") (pin "16") (pinfunction "SCL_16") (pintype "input"))
      (node (ref "U4") (pin "7") (pinfunction "SCL_7") (pintype "input"))
    )
    (net (code "46") (name "SDA") (class "Default")
      (node (ref "J3") (pin "3") (pinfunction "3_3") (pintype "passive"))
      (node (ref "R1_PINH") (pin "1") (pinfunction "1_1") (pintype "passive"))
      (node (ref "SENSOR2") (pin "3") (pinfunction "SDI_3") (pintype "bidirectional"))
      (node (ref "U2") (pin "19") (pinfunction "IO21_19") (pintype "bidirectional"))
      (node (ref "U3") (pin "15") (pinfunction "SDA_15") (pintype "bidirectional"))
      (node (ref "U4") (pin "8") (pinfunction "SDA_8") (pintype "bidirectional"))
    )
    (net (code "47") (name "SRC") (class "Default")
      (node (ref "C4") (pin "2") (pinfunction "2_2") (pintype "passive"))
      (node (ref "D5") (pin "2") (pinfunction "A_2") (pintype "bidirectional"))
      (node (ref "L1") (pin "1") (pinfunction "1_1") (pintype "passive"))
      (node (ref "Q3") (pin "3") (pinfunction "D_3") (pintype "bidirectional"))
    )
    (net (code "48") (name "SS_SD") (class "Default")
      (node (ref "D8") (pin "2") (pinfunction "2_2") (pintype "passive"))
      (node (ref "J4") (pin "P2") (pinfunction "CD/DAT3_P2") (pintype "bidirectional"))
      (node (ref "R10") (pin "1") (pinfunction "1_1") (pintype "passive"))
      (node (ref "U2") (pin "4") (pinfunction "IO4_4") (pintype "bidirectional"))
    )
    (net (code "49") (name "TX") (class "Default")
      (node (ref "TP1") (pin "TP") (pinfunction "TP_TP") (pintype "input"))
      (node (ref "U2") (pin "25") (pinfunction "TXD0/GPIO16_25") (pintype "bidirectional"))
    )
    (net (code "50") (name "USB_D+") (class "Default")
      (node (ref "D1") (pin "1") (pinfunction "I/O1_1_1") (pintype "bidirectional"))
      (node (ref "U2") (pin "14") (pinfunction "IO13_14") (pintype "bidirectional"))
    )
    (net (code "51") (name "USB_D-") (class "Default")
      (node (ref "D1") (pin "3") (pinfunction "I/O2_1_3") (pintype "bidirectional"))
      (node (ref "U2") (pin "13") (pinfunction "IO12_13") (pintype "bidirectional"))
    )
    (net (code "52") (name "VBAT") (class "Default")
      (node (ref "C2_BAT") (pin "1") (pinfunction "1_1") (pintype "passive"))
      (node (ref "MCP73831") (pin "3") (pinfunction "VBAT_3") (pintype "power_in"))
      (node (ref "Q1") (pin "3") (pinfunction "D_3") (pintype "bidirectional"))
      (node (ref "TP3") (pin "TP") (pinfunction "TP_TP") (pintype "input"))
      (node (ref "U4") (pin "2") (pinfunction "CELL_2") (pintype "power_in"))
      (node (ref "U4") (pin "3") (pinfunction "VDD_3") (pintype "power_in"))
    )
    (net (code "53") (name "VBUS") (class "Default")
      (node (ref "C1_BAT") (pin "1") (pinfunction "1_1") (pintype "passive"))
      (node (ref "C4_USB") (pin "1") (pinfunction "1_1") (pintype "passive"))
      (node (ref "C5_USB") (pin "1") (pinfunction "1_1") (pintype "passive"))
      (node (ref "CHG_LED") (pin "A") (pinfunction "A_A") (pintype "passive"))
      (node (ref "D1") (pin "5") (pinfunction "VBUS_5") (pintype "bidirectional"))
      (node (ref "D2") (pin "2") (pinfunction "ANODE_2") (pintype "bidirectional"))
      (node (ref "MCP73831") (pin "4") (pinfunction "VIN_4") (pintype "power_in"))
      (node (ref "PFMF.050.1") (pin "2") (pinfunction "2_2") (pintype "passive"))
      (node (ref "Q1") (pin "1") (pinfunction "G_1") (pintype "bidirectional"))
      (node (ref "R1_PWRUSB") (pin "2") (pinfunction "2_2") (pintype "passive"))
      (node (ref "TP14") (pin "TP") (pinfunction "TP_TP") (pintype "input"))
    )
    (net (code "54") (name "VRTC") (class "Default")
      (node (ref "C10_SUPERCAP") (pin "2") (pinfunction "2_2") (pintype "passive"))
      (node (ref "C8") (pin "1") (pinfunction "1_1") (pintype "passive"))
      (node (ref "R_CAPACITOR") (pin "1") (pinfunction "1_1") (pintype "passive"))
      (node (ref "U3") (pin "14") (pinfunction "VBAT_14") (pintype "power_in"))
    )
    (net (code "55") (name "VUSB") (class "Default")
      (node (ref "J2") (pin "A4") (pinfunction "A4_A4") (pintype "bidirectional"))
      (node (ref "J2") (pin "A9") (pinfunction "A9_A9") (pintype "bidirectional"))
      (node (ref "J2") (pin "B4") (pinfunction "B4_B4") (pintype "bidirectional"))
      (node (ref "J2") (pin "B9") (pinfunction "B9_B9") (pintype "bidirectional"))
      (node (ref "PFMF.050.1") (pin "1") (pinfunction "1_1") (pintype "passive"))
    )
    (net (code "56") (name "unconnected-(IC1-NC-Pad4)") (class "Default")
      (node (ref "IC1") (pin "4") (pinfunction "NC_4") (pintype "no_connect"))
    )
    (net (code "57") (name "unconnected-(IC4-NC-Pad4)") (class "Default")
      (node (ref "IC4") (pin "4") (pinfunction "NC_4") (pintype "no_connect"))
    )
    (net (code "58") (name "unconnected-(J1-Pad1)") (class "Default")
      (node (ref "J1") (pin "1") (pinfunction "1_1") (pintype "bidirectional"))
    )
    (net (code "59") (name "unconnected-(J1-Pad6)") (class "Default")
      (node (ref "J1") (pin "6") (pinfunction "6_6") (pintype "bidirectional"))
    )
    (net (code "60") (name "unconnected-(J1-Pad7)") (class "Default")
      (node (ref "J1") (pin "7") (pinfunction "7_7") (pintype "bidirectional"))
    )
    (net (code "61") (name "unconnected-(J2-PadA8)") (class "Default")
      (node (ref "J2") (pin "A8") (pinfunction "A8_A8") (pintype "bidirectional"))
    )
    (net (code "62") (name "unconnected-(J2-PadB8)") (class "Default")
      (node (ref "J2") (pin "B8") (pinfunction "B8_B8") (pintype "bidirectional"))
    )
    (net (code "63") (name "unconnected-(J4-DAT1-PadP8)") (class "Default")
      (node (ref "J4") (pin "P8") (pinfunction "DAT1_P8") (pintype "bidirectional"))
    )
    (net (code "64") (name "unconnected-(J4-DAT2-PadP1)") (class "Default")
      (node (ref "J4") (pin "P1") (pinfunction "DAT2_P1") (pintype "bidirectional"))
    )
    (net (code "65") (name "unconnected-(J4-DETECTION_1-PadS1)") (class "Default")
      (node (ref "J4") (pin "S1") (pinfunction "DETECTION_1_S1") (pintype "bidirectional"))
    )
    (net (code "66") (name "unconnected-(J4-DETECTION_2-PadS2)") (class "Default")
      (node (ref "J4") (pin "S2") (pinfunction "DETECTION_2_S2") (pintype "bidirectional"))
    )
    (net (code "67") (name "unconnected-(U2-NC-Pad22)") (class "Default")
      (node (ref "U2") (pin "22") (pinfunction "NC_22") (pintype "no_connect"))
    )
    (net (code "68") (name "unconnected-(U4-~{ALERT}-Pad5)") (class "Default")
      (node (ref "U4") (pin "5") (pinfunction "~{ALERT}_5") (pintype "output"))
    )
  )
)
